# Xtal.net
KiCad netlist of a schematic drawn in Altium Designer
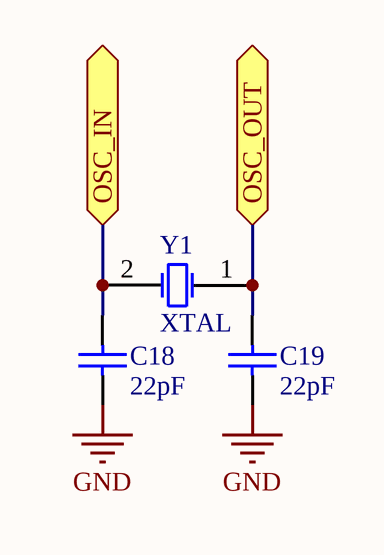
[diagram p0: Xtal.SchDoc]

(export (version "E")
  (design (tool "Eeschema 10.0.6"))
  (components
    (comp (ref "C18")
      (value "22pF")
      (footprint "2012[0805]")
      (description "Capacitor")
      (fields (field (name "Comment") "Cap_UP") (field (name "PUBLISHER") "Altium Limited"))
      (libsource (lib "KN2CLib") (part "Cap_UP"))
    )
    (comp (ref "C19")
      (value "22pF")
      (footprint "2012[0805]")
      (description "Capacitor")
      (fields (field (name "Comment") "Cap_UP") (field (name "PUBLISHER") "Altium Limited"))
      (libsource (lib "KN2CLib") (part "Cap_UP"))
    )
    (comp (ref "Y1")
      (value "XTAL")
      (footprint "XTALL")
      (description "Crystal Oscillator")
      (fields (field (name "PUBLISHER") "Altium Limited"))
      (libsource (lib "KN2CLib") (part "XTAL"))
    )
  )
  (nets
    (net (code "1") (name "/OSC_IN") (class "Default")
      (node (ref "C18") (pin "1") (pinfunction "1_1") (pintype "passive"))
      (node (ref "Y1") (pin "2") (pinfunction "OSC2_2") (pintype "passive"))
    )
    (net (code "2") (name "/OSC_OUT") (class "Default")
      (node (ref "C19") (pin "1") (pinfunction "1_1") (pintype "passive"))
      (node (ref "Y1") (pin "1") (pinfunction "OSC1_1") (pintype "passive"))
    )
    (net (code "3") (name "GND") (class "Default")
      (node (ref "C18") (pin "2") (pinfunction "2_2") (pintype "passive"))
      (node (ref "C19") (pin "2") (pinfunction "2_2") (pintype "passive"))
    )
  )
)
